# Main.net
KiCad netlist of a schematic drawn in Altium Designer
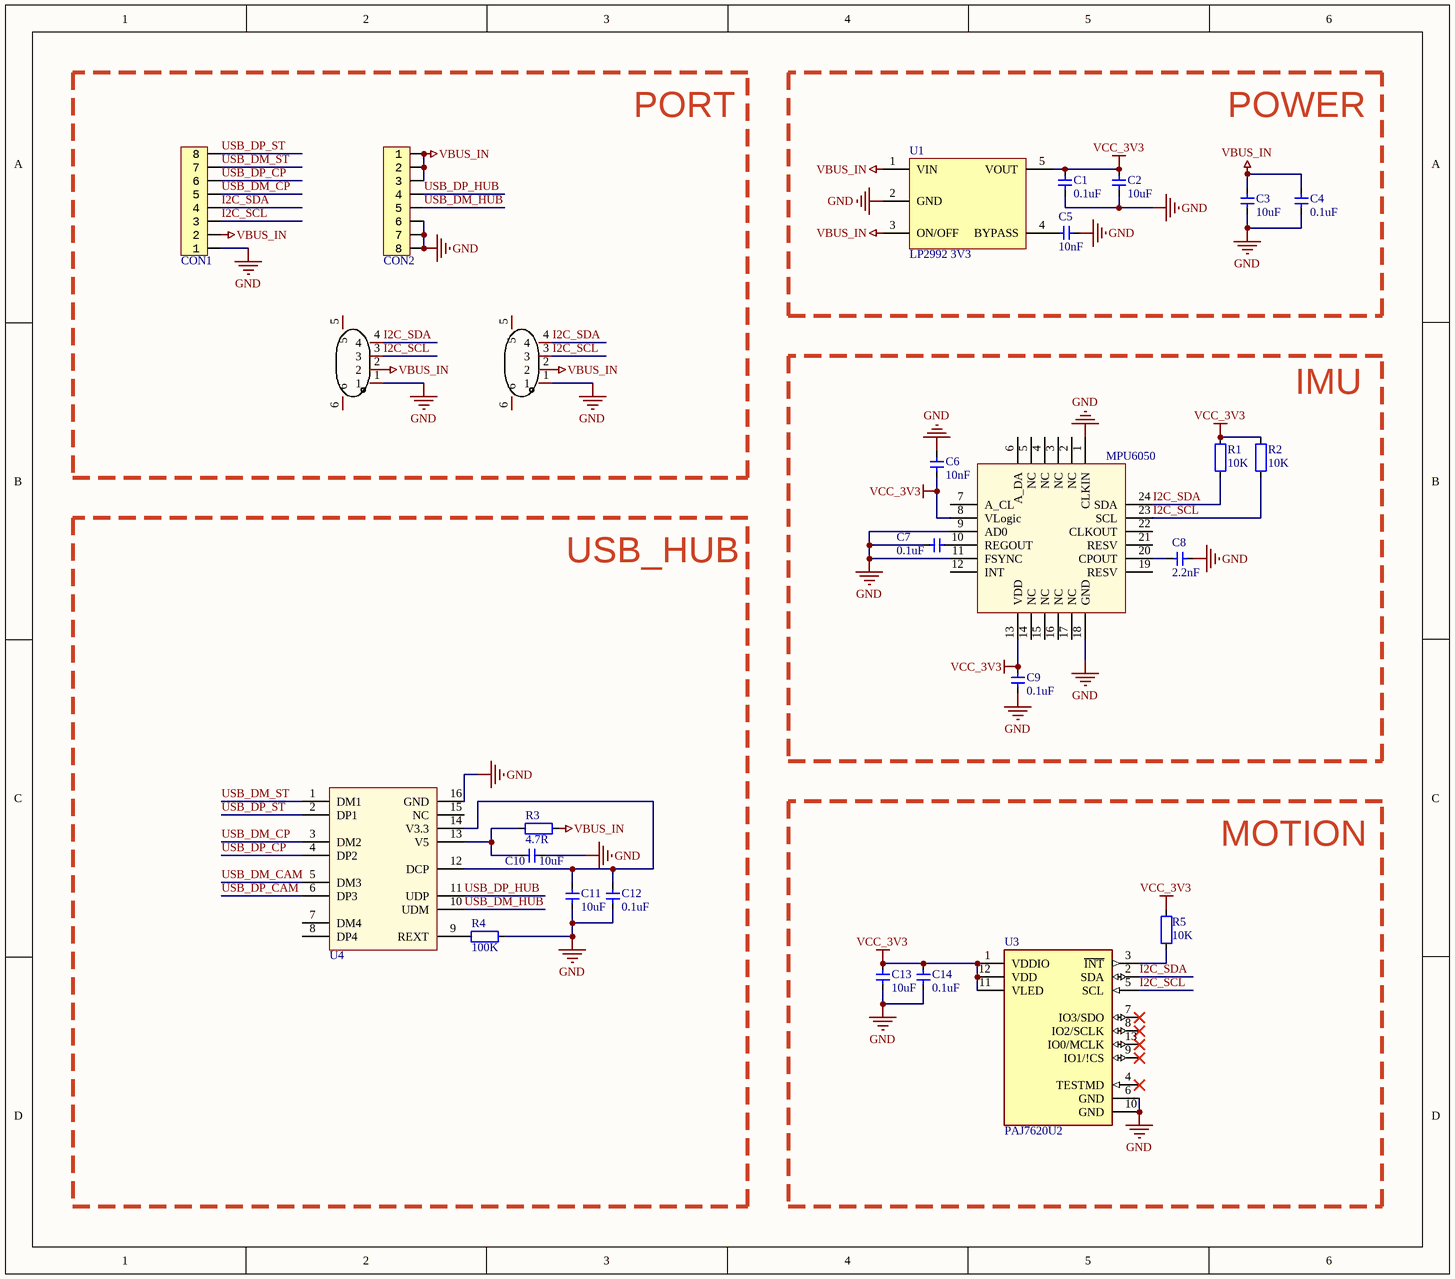
[diagram p0: Main.SchDoc]

(export (version "E")
  (design (tool "Eeschema 10.0.6"))
  (components
    (comp (ref "C1")
      (value "0.1uF")
      (footprint "CAP_0402")
      (description "Capacitor")
      (libsource (lib "MyPcbLib") (part "电容-0402"))
    )
    (comp (ref "C2")
      (value "10uF")
      (footprint "CAP_0402")
      (description "Capacitor")
      (libsource (lib "MyPcbLib") (part "电容-0402"))
    )
    (comp (ref "C3")
      (value "10uF")
      (footprint "CAP_0402")
      (description "Capacitor")
      (libsource (lib "MyPcbLib") (part "电容-0402"))
    )
    (comp (ref "C4")
      (value "0.1uF")
      (footprint "CAP_0402")
      (description "Capacitor")
      (libsource (lib "MyPcbLib") (part "电容-0402"))
    )
    (comp (ref "C5")
      (value "10nF")
      (footprint "CAP_0402")
      (description "Capacitor")
      (libsource (lib "MyPcbLib") (part "电容-0402"))
    )
    (comp (ref "C6")
      (value "10nF")
      (footprint "CAP_0402")
      (description "Capacitor")
      (libsource (lib "MyPcbLib") (part "电容-0402"))
    )
    (comp (ref "C7")
      (value "0.1uF")
      (footprint "CAP_0402")
      (description "Capacitor")
      (libsource (lib "MyPcbLib") (part "电容-0402"))
    )
    (comp (ref "C8")
      (value "2.2nF")
      (footprint "CAP_0402")
      (description "Capacitor")
      (libsource (lib "MyPcbLib") (part "电容-0402"))
    )
    (comp (ref "C9")
      (value "0.1uF")
      (footprint "CAP_0402")
      (description "Capacitor")
      (libsource (lib "MyPcbLib") (part "电容-0402"))
    )
    (comp (ref "C10")
      (value "10uF")
      (footprint "CAP_0402")
      (description "Capacitor")
      (libsource (lib "MyPcbLib") (part "电容-0402"))
    )
    (comp (ref "C11")
      (value "10uF")
      (footprint "CAP_0402")
      (description "Capacitor")
      (libsource (lib "MyPcbLib") (part "电容-0402"))
    )
    (comp (ref "C12")
      (value "0.1uF")
      (footprint "CAP_0402")
      (description "Capacitor")
      (libsource (lib "MyPcbLib") (part "电容-0402"))
    )
    (comp (ref "C13")
      (value "10uF")
      (footprint "CAP_0402")
      (description "Capacitor")
      (libsource (lib "MyPcbLib") (part "电容-0402"))
    )
    (comp (ref "C14")
      (value "0.1uF")
      (footprint "CAP_0402")
      (description "Capacitor")
      (libsource (lib "MyPcbLib") (part "电容-0402"))
    )
    (comp (ref "CON1")
      (value "FFC_0.5_8")
      (footprint "FFC_0.5_8")
      (description "FFC")
      (libsource (lib "KitSprout") (part "FFC_0.5_8"))
    )
    (comp (ref "CON2")
      (value "FFC_0.5_8")
      (footprint "FFC_0.5_8")
      (description "FFC")
      (libsource (lib "") (part "FFC_0.5_8_1"))
    )
    (comp (ref "FPC1")
      (value "0.5K-DX-4PWB")
      (footprint "FPC-SMD_4P-P0.50_DEALON_0.5K-DX-4PWB")
      (fields (field (name "MANUFACTURER") "HDGC(华德共创)"))
      (libsource (lib "altium-import") (part "root_2_0.5K-DX-4PWB_"))
    )
    (comp (ref "FPC2")
      (value "0.5K-DX-4PWB")
      (footprint "FPC-SMD_4P-P0.50_DEALON_0.5K-DX-4PWB")
      (fields (field (name "MANUFACTURER") "HDGC(华德共创)"))
      (libsource (lib "altium-import") (part "root_2_0.5K-DX-4PWB_"))
    )
    (comp (ref "R1")
      (value "10K")
      (footprint "RES_0402")
      (description "Resistor")
      (libsource (lib "") (part "电阻-0402_1"))
    )
    (comp (ref "R2")
      (value "10K")
      (footprint "RES_0402")
      (description "Resistor")
      (libsource (lib "") (part "电阻-0402_1"))
    )
    (comp (ref "R3")
      (value "4.7R")
      (footprint "RES_0402")
      (description "Resistor")
      (libsource (lib "") (part "电阻-0402_2"))
    )
    (comp (ref "R4")
      (value "100K")
      (footprint "RES_0402")
      (description "Resistor")
      (libsource (lib "") (part "电阻-0402_2"))
    )
    (comp (ref "R5")
      (value "10K")
      (footprint "RES_0402")
      (description "Resistor")
      (libsource (lib "MyPcbLib") (part "电阻-0402"))
    )
    (comp (ref "U1")
      (value "LP2992 3V3")
      (footprint "SOT23-5")
      (description "LDO")
      (libsource (lib "MyPcbLib") (part "LP2992"))
    )
    (comp (ref "U2")
      (value "MPU6050")
      (footprint "QFN-24")
      (description "六轴传感器")
      (libsource (lib "mLib") (part "MPU6050"))
    )
    (comp (ref "U3")
      (value "PAJ7620U2")
      (footprint "PAJ7620U2")
      (description "module sensorPAJ7620U2 : 54/TRAY, 5400/BOX, 32400/CARTON")
      (fields (field (name "MF") "Pixart"))
      (libsource (lib "MyPcbLib") (part "PAJ7620U2"))
    )
    (comp (ref "U4")
      (value "HS8836A")
      (footprint "SO-16N")
      (description "USB2.0 HUB")
      (libsource (lib "MyPcbLib") (part "HS8836A"))
    )
  )
  (nets
    (net (code "1") (name "/I2C_SCL") (class "Default")
      (node (ref "CON1") (pin "3") (pinfunction "3_3") (pintype "passive"))
      (node (ref "FPC1") (pin "3") (pinfunction "3_3") (pintype "passive"))
      (node (ref "FPC2") (pin "3") (pinfunction "3_3") (pintype "passive"))
      (node (ref "R2") (pin "1") (pinfunction "1_1") (pintype "passive"))
      (node (ref "U2") (pin "23") (pinfunction "SCL_23") (pintype "passive"))
      (node (ref "U3") (pin "5") (pinfunction "SCL_5") (pintype "input"))
    )
    (net (code "2") (name "/I2C_SDA") (class "Default")
      (node (ref "CON1") (pin "4") (pinfunction "4_4") (pintype "passive"))
      (node (ref "FPC1") (pin "4") (pinfunction "4_4") (pintype "passive"))
      (node (ref "FPC2") (pin "4") (pinfunction "4_4") (pintype "passive"))
      (node (ref "R1") (pin "1") (pinfunction "1_1") (pintype "passive"))
      (node (ref "U2") (pin "24") (pinfunction "SDA_24") (pintype "passive"))
      (node (ref "U3") (pin "2") (pinfunction "SDA_2") (pintype "bidirectional"))
    )
    (net (code "3") (name "/USB_DM_CAM") (class "Default")
      (node (ref "U4") (pin "5") (pinfunction "DM3_5") (pintype "passive"))
    )
    (net (code "4") (name "/USB_DM_CP") (class "Default")
      (node (ref "CON1") (pin "5") (pinfunction "5_5") (pintype "passive"))
      (node (ref "U4") (pin "3") (pinfunction "DM2_3") (pintype "passive"))
    )
    (net (code "5") (name "/USB_DM_HUB") (class "Default")
      (node (ref "CON2") (pin "5") (pinfunction "5_5") (pintype "passive"))
      (node (ref "U4") (pin "10") (pinfunction "UDM_10") (pintype "passive"))
    )
    (net (code "6") (name "/USB_DM_ST") (class "Default")
      (node (ref "CON1") (pin "7") (pinfunction "7_7") (pintype "passive"))
      (node (ref "U4") (pin "1") (pinfunction "DM1_1") (pintype "passive"))
    )
    (net (code "7") (name "/USB_DP_CAM") (class "Default")
      (node (ref "U4") (pin "6") (pinfunction "DP3_6") (pintype "passive"))
    )
    (net (code "8") (name "/USB_DP_CP") (class "Default")
      (node (ref "CON1") (pin "6") (pinfunction "6_6") (pintype "passive"))
      (node (ref "U4") (pin "4") (pinfunction "DP2_4") (pintype "passive"))
    )
    (net (code "9") (name "/USB_DP_HUB") (class "Default")
      (node (ref "CON2") (pin "4") (pinfunction "4_4") (pintype "passive"))
      (node (ref "U4") (pin "11") (pinfunction "UDP_11") (pintype "passive"))
    )
    (net (code "10") (name "/USB_DP_ST") (class "Default")
      (node (ref "CON1") (pin "8") (pinfunction "8_8") (pintype "passive"))
      (node (ref "U4") (pin "2") (pinfunction "DP1_2") (pintype "passive"))
    )
    (net (code "11") (name "GND") (class "Default")
      (node (ref "C1") (pin "1") (pinfunction "1_1") (pintype "passive"))
      (node (ref "C10") (pin "1") (pinfunction "1_1") (pintype "passive"))
      (node (ref "C11") (pin "2") (pinfunction "2_2") (pintype "passive"))
      (node (ref "C12") (pin "2") (pinfunction "2_2") (pintype "passive"))
      (node (ref "C13") (pin "2") (pinfunction "2_2") (pintype "passive"))
      (node (ref "C14") (pin "2") (pinfunction "2_2") (pintype "passive"))
      (node (ref "C2") (pin "1") (pinfunction "1_1") (pintype "passive"))
      (node (ref "C3") (pin "1") (pinfunction "1_1") (pintype "passive"))
      (node (ref "C4") (pin "1") (pinfunction "1_1") (pintype "passive"))
      (node (ref "C5") (pin "1") (pinfunction "1_1") (pintype "passive"))
      (node (ref "C6") (pin "2") (pinfunction "2_2") (pintype "passive"))
      (node (ref "C7") (pin "2") (pinfunction "2_2") (pintype "passive"))
      (node (ref "C8") (pin "1") (pinfunction "1_1") (pintype "passive"))
      (node (ref "C9") (pin "1") (pinfunction "1_1") (pintype "passive"))
      (node (ref "CON1") (pin "1") (pinfunction "1_1") (pintype "passive"))
      (node (ref "CON2") (pin "6") (pinfunction "6_6") (pintype "passive"))
      (node (ref "CON2") (pin "7") (pinfunction "7_7") (pintype "passive"))
      (node (ref "CON2") (pin "8") (pinfunction "8_8") (pintype "passive"))
      (node (ref "FPC1") (pin "1") (pinfunction "1_1") (pintype "passive"))
      (node (ref "FPC2") (pin "1") (pinfunction "1_1") (pintype "passive"))
      (node (ref "R4") (pin "1") (pinfunction "1_1") (pintype "passive"))
      (node (ref "U1") (pin "2") (pinfunction "GND_2") (pintype "passive"))
      (node (ref "U2") (pin "1") (pinfunction "CLKIN_1") (pintype "passive"))
      (node (ref "U2") (pin "11") (pinfunction "FSYNC_11") (pintype "passive"))
      (node (ref "U2") (pin "18") (pinfunction "GND_18") (pintype "passive"))
      (node (ref "U2") (pin "9") (pinfunction "AD0_9") (pintype "passive"))
      (node (ref "U3") (pin "10") (pinfunction "GND_10") (pintype "passive"))
      (node (ref "U3") (pin "6") (pinfunction "GND_6") (pintype "passive"))
      (node (ref "U4") (pin "16") (pinfunction "GND_16") (pintype "passive"))
    )
    (net (code "12") (name "Net-(U1-BYPASS)") (class "Default")
      (node (ref "C5") (pin "2") (pinfunction "2_2") (pintype "passive"))
      (node (ref "U1") (pin "4") (pinfunction "BYPASS_4") (pintype "passive"))
    )
    (net (code "13") (name "Net-(U2-CPOUT)") (class "Default")
      (node (ref "C8") (pin "2") (pinfunction "2_2") (pintype "passive"))
      (node (ref "U2") (pin "20") (pinfunction "CPOUT_20") (pintype "passive"))
    )
    (net (code "14") (name "Net-(U2-REGOUT)") (class "Default")
      (node (ref "C7") (pin "1") (pinfunction "1_1") (pintype "passive"))
      (node (ref "U2") (pin "10") (pinfunction "REGOUT_10") (pintype "passive"))
    )
    (net (code "15") (name "Net-(U3-~{INT})") (class "Default")
      (node (ref "R5") (pin "2") (pinfunction "2_2") (pintype "passive"))
      (node (ref "U3") (pin "3") (pinfunction "~{INT}_3") (pintype "output"))
    )
    (net (code "16") (name "Net-(U4-DCP)") (class "Default")
      (node (ref "C11") (pin "1") (pinfunction "1_1") (pintype "passive"))
      (node (ref "C12") (pin "1") (pinfunction "1_1") (pintype "passive"))
      (node (ref "U4") (pin "12") (pinfunction "DCP_12") (pintype "passive"))
      (node (ref "U4") (pin "14") (pinfunction "V3.3_14") (pintype "passive"))
    )
    (net (code "17") (name "Net-(U4-REXT)") (class "Default")
      (node (ref "R4") (pin "2") (pinfunction "2_2") (pintype "passive"))
      (node (ref "U4") (pin "9") (pinfunction "REXT_9") (pintype "passive"))
    )
    (net (code "18") (name "Net-(U4-V5)") (class "Default")
      (node (ref "C10") (pin "2") (pinfunction "2_2") (pintype "passive"))
      (node (ref "R3") (pin "2") (pinfunction "2_2") (pintype "passive"))
      (node (ref "U4") (pin "13") (pinfunction "V5_13") (pintype "passive"))
    )
    (net (code "19") (name "VBUS_IN") (class "Default")
      (node (ref "C3") (pin "2") (pinfunction "2_2") (pintype "passive"))
      (node (ref "C4") (pin "2") (pinfunction "2_2") (pintype "passive"))
      (node (ref "CON1") (pin "2") (pinfunction "2_2") (pintype "passive"))
      (node (ref "CON2") (pin "1") (pinfunction "1_1") (pintype "passive"))
      (node (ref "CON2") (pin "2") (pinfunction "2_2") (pintype "passive"))
      (node (ref "CON2") (pin "3") (pinfunction "3_3") (pintype "passive"))
      (node (ref "FPC1") (pin "2") (pinfunction "2_2") (pintype "passive"))
      (node (ref "FPC2") (pin "2") (pinfunction "2_2") (pintype "passive"))
      (node (ref "R3") (pin "1") (pinfunction "1_1") (pintype "passive"))
      (node (ref "U1") (pin "1") (pinfunction "VIN_1") (pintype "passive"))
      (node (ref "U1") (pin "3") (pinfunction "ON/OFF_3") (pintype "passive"))
    )
    (net (code "20") (name "VCC_3V3") (class "Default")
      (node (ref "C1") (pin "2") (pinfunction "2_2") (pintype "passive"))
      (node (ref "C13") (pin "1") (pinfunction "1_1") (pintype "passive"))
      (node (ref "C14") (pin "1") (pinfunction "1_1") (pintype "passive"))
      (node (ref "C2") (pin "2") (pinfunction "2_2") (pintype "passive"))
      (node (ref "C6") (pin "1") (pinfunction "1_1") (pintype "passive"))
      (node (ref "C9") (pin "2") (pinfunction "2_2") (pintype "passive"))
      (node (ref "R1") (pin "2") (pinfunction "2_2") (pintype "passive"))
      (node (ref "R2") (pin "2") (pinfunction "2_2") (pintype "passive"))
      (node (ref "R5") (pin "1") (pinfunction "1_1") (pintype "passive"))
      (node (ref "U1") (pin "5") (pinfunction "VOUT_5") (pintype "passive"))
      (node (ref "U2") (pin "13") (pinfunction "VDD_13") (pintype "passive"))
      (node (ref "U2") (pin "8") (pinfunction "VLogic_8") (pintype "passive"))
      (node (ref "U3") (pin "1") (pinfunction "VDDIO_1") (pintype "power_in"))
      (node (ref "U3") (pin "11") (pinfunction "VLED_11") (pintype "power_in"))
      (node (ref "U3") (pin "12") (pinfunction "VDD_12") (pintype "power_in"))
    )
    (net (code "21") (name "unconnected-(FPC1-Pad5)") (class "Default")
      (node (ref "FPC1") (pin "5") (pinfunction "5_5") (pintype "passive"))
    )
    (net (code "22") (name "unconnected-(FPC1-Pad6)") (class "Default")
      (node (ref "FPC1") (pin "6") (pinfunction "6_6") (pintype "passive"))
    )
    (net (code "23") (name "unconnected-(FPC2-Pad5)") (class "Default")
      (node (ref "FPC2") (pin "5") (pinfunction "5_5") (pintype "passive"))
    )
    (net (code "24") (name "unconnected-(FPC2-Pad6)") (class "Default")
      (node (ref "FPC2") (pin "6") (pinfunction "6_6") (pintype "passive"))
    )
    (net (code "25") (name "unconnected-(U2-A_CL-Pad7)") (class "Default")
      (node (ref "U2") (pin "7") (pinfunction "A_CL_7") (pintype "passive"))
    )
    (net (code "26") (name "unconnected-(U2-A_DA-Pad6)") (class "Default")
      (node (ref "U2") (pin "6") (pinfunction "A_DA_6") (pintype "passive"))
    )
    (net (code "27") (name "unconnected-(U2-CLKOUT-Pad22)") (class "Default")
      (node (ref "U2") (pin "22") (pinfunction "CLKOUT_22") (pintype "passive"))
    )
    (net (code "28") (name "unconnected-(U2-INT-Pad12)") (class "Default")
      (node (ref "U2") (pin "12") (pinfunction "INT_12") (pintype "passive"))
    )
    (net (code "29") (name "unconnected-(U2-NC-Pad2)") (class "Default")
      (node (ref "U2") (pin "2") (pinfunction "NC_2") (pintype "passive"))
    )
    (net (code "30") (name "unconnected-(U2-NC-Pad3)") (class "Default")
      (node (ref "U2") (pin "3") (pinfunction "NC_3") (pintype "passive"))
    )
    (net (code "31") (name "unconnected-(U2-NC-Pad4)") (class "Default")
      (node (ref "U2") (pin "4") (pinfunction "NC_4") (pintype "passive"))
    )
    (net (code "32") (name "unconnected-(U2-NC-Pad5)") (class "Default")
      (node (ref "U2") (pin "5") (pinfunction "NC_5") (pintype "passive"))
    )
    (net (code "33") (name "unconnected-(U2-NC-Pad14)") (class "Default")
      (node (ref "U2") (pin "14") (pinfunction "NC_14") (pintype "passive"))
    )
    (net (code "34") (name "unconnected-(U2-NC-Pad15)") (class "Default")
      (node (ref "U2") (pin "15") (pinfunction "NC_15") (pintype "passive"))
    )
    (net (code "35") (name "unconnected-(U2-NC-Pad16)") (class "Default")
      (node (ref "U2") (pin "16") (pinfunction "NC_16") (pintype "passive"))
    )
    (net (code "36") (name "unconnected-(U2-NC-Pad17)") (class "Default")
      (node (ref "U2") (pin "17") (pinfunction "NC_17") (pintype "passive"))
    )
    (net (code "37") (name "unconnected-(U2-RESV-Pad19)") (class "Default")
      (node (ref "U2") (pin "19") (pinfunction "RESV_19") (pintype "passive"))
    )
    (net (code "38") (name "unconnected-(U2-RESV-Pad21)") (class "Default")
      (node (ref "U2") (pin "21") (pinfunction "RESV_21") (pintype "passive"))
    )
    (net (code "39") (name "unconnected-(U3-IO0{slash}MCLK-Pad13)") (class "Default")
      (node (ref "U3") (pin "13") (pinfunction "IO0/MCLK_13") (pintype "bidirectional+no_connect"))
    )
    (net (code "40") (name "unconnected-(U3-IO1{slash}!CS-Pad9)") (class "Default")
      (node (ref "U3") (pin "9") (pinfunction "IO1/!CS_9") (pintype "bidirectional+no_connect"))
    )
    (net (code "41") (name "unconnected-(U3-IO2{slash}SCLK-Pad8)") (class "Default")
      (node (ref "U3") (pin "8") (pinfunction "IO2/SCLK_8") (pintype "bidirectional+no_connect"))
    )
    (net (code "42") (name "unconnected-(U3-IO3{slash}SDO-Pad7)") (class "Default")
      (node (ref "U3") (pin "7") (pinfunction "IO3/SDO_7") (pintype "bidirectional+no_connect"))
    )
    (net (code "43") (name "unconnected-(U3-TESTMD-Pad4)") (class "Default")
      (node (ref "U3") (pin "4") (pinfunction "TESTMD_4") (pintype "input+no_connect"))
    )
    (net (code "44") (name "unconnected-(U4-DM4-Pad7)") (class "Default")
      (node (ref "U4") (pin "7") (pinfunction "DM4_7") (pintype "passive"))
    )
    (net (code "45") (name "unconnected-(U4-DP4-Pad8)") (class "Default")
      (node (ref "U4") (pin "8") (pinfunction "DP4_8") (pintype "passive"))
    )
    (net (code "46") (name "unconnected-(U4-NC-Pad15)") (class "Default")
      (node (ref "U4") (pin "15") (pinfunction "NC_15") (pintype "passive"))
    )
  )
)
